# SWD.net
KiCad netlist of a schematic drawn in Altium Designer
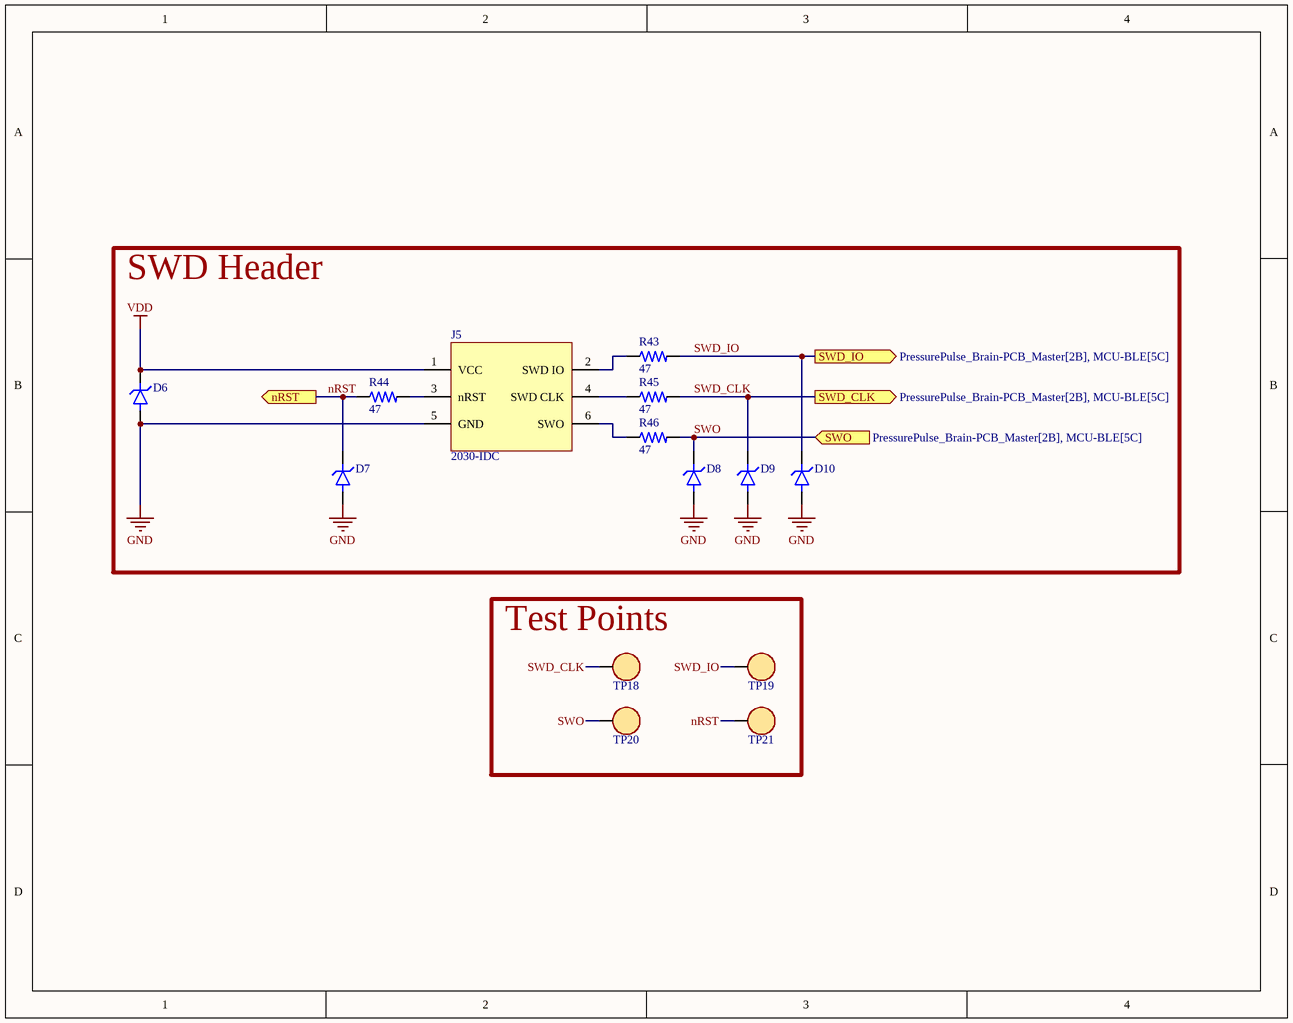
[diagram p0: SWD.SchDoc]

(export (version "E")
  (design (tool "Eeschema 10.0.6"))
  (components
    (comp (ref "D6")
      (value "RCLAMP0521P.TCT")
      (footprint "PressurePulse:BDFN2C051V40")
      (description "25V Clamp 4A (8/20µs) Ipp Tvs Diode Surface Mount SLP1006P2")
      (fields (field (name "MFR") "BORN"))
      (libsource (lib "PressurePulse") (part "TVS DIODE"))
    )
    (comp (ref "D7")
      (value "RCLAMP0521P.TCT")
      (footprint "PressurePulse:BDFN2C051V40")
      (description "25V Clamp 4A (8/20µs) Ipp Tvs Diode Surface Mount SLP1006P2")
      (fields (field (name "MFR") "BORN"))
      (libsource (lib "PressurePulse") (part "TVS DIODE"))
    )
    (comp (ref "D8")
      (value "RCLAMP0521P.TCT")
      (footprint "PressurePulse:BDFN2C051V40")
      (description "25V Clamp 4A (8/20µs) Ipp Tvs Diode Surface Mount SLP1006P2")
      (fields (field (name "MFR") "BORN"))
      (libsource (lib "PressurePulse") (part "TVS DIODE"))
    )
    (comp (ref "D9")
      (value "RCLAMP0521P.TCT")
      (footprint "PressurePulse:BDFN2C051V40")
      (description "25V Clamp 4A (8/20µs) Ipp Tvs Diode Surface Mount SLP1006P2")
      (fields (field (name "MFR") "BORN"))
      (libsource (lib "PressurePulse") (part "TVS DIODE"))
    )
    (comp (ref "D10")
      (value "RCLAMP0521P.TCT")
      (footprint "PressurePulse:BDFN2C051V40")
      (description "25V Clamp 4A (8/20µs) Ipp Tvs Diode Surface Mount SLP1006P2")
      (fields (field (name "MFR") "BORN"))
      (libsource (lib "PressurePulse") (part "TVS DIODE"))
    )
    (comp (ref "J5")
      (value "2030-IDC")
      (footprint "PressurePulse:TAG CONNECT TC2030IDC - NO 3D MODEL")
      (description "TAG CONNECT 2030-IDC")
      (fields (field (name "MFR") "Tag Connect"))
      (libsource (lib "PressurePulse") (part "TAG CONNECT 2030-IDC"))
    )
    (comp (ref "R43")
      (value "47")
      (footprint "PressurePulse:0402R")
      (description "Resistor")
      (fields (field (name "Comment") "RES"))
      (libsource (lib "PressurePulse") (part "RES"))
    )
    (comp (ref "R44")
      (value "47")
      (footprint "PressurePulse:0402R")
      (description "Resistor")
      (fields (field (name "Comment") "RES"))
      (libsource (lib "PressurePulse") (part "RES"))
    )
    (comp (ref "R45")
      (value "47")
      (footprint "PressurePulse:0402R")
      (description "Resistor")
      (fields (field (name "Comment") "RES"))
      (libsource (lib "PressurePulse") (part "RES"))
    )
    (comp (ref "R46")
      (value "47")
      (footprint "PressurePulse:0402R")
      (description "Resistor")
      (fields (field (name "Comment") "RES"))
      (libsource (lib "PressurePulse") (part "RES"))
    )
    (comp (ref "TP18")
      (value "RH-5019")
      (footprint "PressurePulse:TP - RH-5019")
      (fields (field (name "MFR") "ronghe"))
      (libsource (lib "PressurePulse") (part "TEST POINT"))
    )
    (comp (ref "TP19")
      (value "RH-5019")
      (footprint "PressurePulse:TP - RH-5019")
      (fields (field (name "MFR") "ronghe"))
      (libsource (lib "PressurePulse") (part "TEST POINT"))
    )
    (comp (ref "TP20")
      (value "RH-5019")
      (footprint "PressurePulse:TP - RH-5019")
      (fields (field (name "MFR") "ronghe"))
      (libsource (lib "PressurePulse") (part "TEST POINT"))
    )
    (comp (ref "TP21")
      (value "RH-5019")
      (footprint "PressurePulse:TP - RH-5019")
      (fields (field (name "MFR") "ronghe"))
      (libsource (lib "PressurePulse") (part "TEST POINT"))
    )
  )
  (nets
    (net (code "1") (name "/SWD_CLK") (class "Default")
      (node (ref "D9") (pin "K") (pinfunction "K_K") (pintype "passive"))
      (node (ref "R45") (pin "2") (pinfunction "2_2") (pintype "passive"))
      (node (ref "TP18") (pin "1") (pinfunction "1_1") (pintype "passive"))
    )
    (net (code "2") (name "/SWD_IO") (class "Default")
      (node (ref "D10") (pin "K") (pinfunction "K_K") (pintype "passive"))
      (node (ref "R43") (pin "2") (pinfunction "2_2") (pintype "passive"))
      (node (ref "TP19") (pin "1") (pinfunction "1_1") (pintype "passive"))
    )
    (net (code "3") (name "/SWO") (class "Default")
      (node (ref "D8") (pin "K") (pinfunction "K_K") (pintype "passive"))
      (node (ref "R46") (pin "2") (pinfunction "2_2") (pintype "passive"))
      (node (ref "TP20") (pin "1") (pinfunction "1_1") (pintype "passive"))
    )
    (net (code "4") (name "/nRST") (class "Default")
      (node (ref "D7") (pin "K") (pinfunction "K_K") (pintype "passive"))
      (node (ref "R44") (pin "1") (pinfunction "1_1") (pintype "passive"))
      (node (ref "TP21") (pin "1") (pinfunction "1_1") (pintype "passive"))
    )
    (net (code "5") (name "GND") (class "Default")
      (node (ref "D10") (pin "A") (pinfunction "A_A") (pintype "passive"))
      (node (ref "D6") (pin "A") (pinfunction "A_A") (pintype "passive"))
      (node (ref "D7") (pin "A") (pinfunction "A_A") (pintype "passive"))
      (node (ref "D8") (pin "A") (pinfunction "A_A") (pintype "passive"))
      (node (ref "D9") (pin "A") (pinfunction "A_A") (pintype "passive"))
      (node (ref "J5") (pin "5") (pinfunction "GND_5") (pintype "passive"))
    )
    (net (code "6") (name "Net-(J5-SWD_CLK)") (class "Default")
      (node (ref "J5") (pin "4") (pinfunction "SWD_CLK_4") (pintype "passive"))
      (node (ref "R45") (pin "1") (pinfunction "1_1") (pintype "passive"))
    )
    (net (code "7") (name "Net-(J5-SWD_IO)") (class "Default")
      (node (ref "J5") (pin "2") (pinfunction "SWD_IO_2") (pintype "passive"))
      (node (ref "R43") (pin "1") (pinfunction "1_1") (pintype "passive"))
    )
    (net (code "8") (name "Net-(J5-SWO)") (class "Default")
      (node (ref "J5") (pin "6") (pinfunction "SWO_6") (pintype "passive"))
      (node (ref "R46") (pin "1") (pinfunction "1_1") (pintype "passive"))
    )
    (net (code "9") (name "Net-(J5-nRST)") (class "Default")
      (node (ref "J5") (pin "3") (pinfunction "nRST_3") (pintype "passive"))
      (node (ref "R44") (pin "2") (pinfunction "2_2") (pintype "passive"))
    )
    (net (code "10") (name "VDD") (class "Default")
      (node (ref "D6") (pin "K") (pinfunction "K_K") (pintype "passive"))
      (node (ref "J5") (pin "1") (pinfunction "VCC_1") (pintype "passive"))
    )
  )
)
